# controller_02.net
KiCad netlist of a schematic drawn in EAGLE
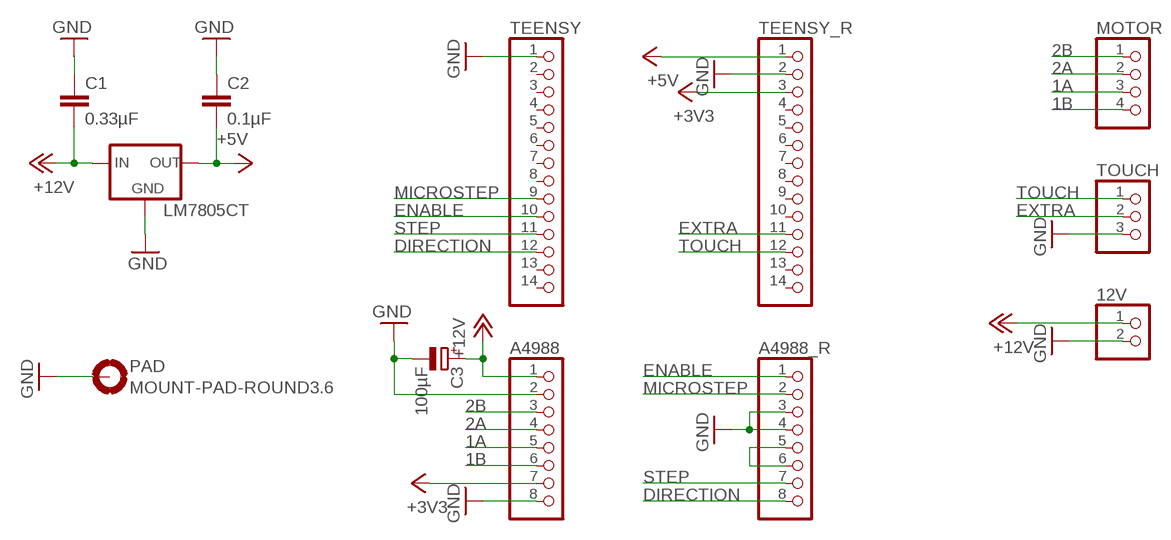
[diagram p0: schematic, sheet 1]

(export (version "E")
  (design (tool "Eeschema 10.0.6"))
  (components
    (comp (ref "12V")
      (value "PINHD-1X2")
      (footprint "eagle-import:1X02")
      (libsource (lib "eagle-import") (part "PINHD-1X2"))
    )
    (comp (ref "A4988")
      (value "PINHD-1X8")
      (footprint "eagle-import:1X08")
      (libsource (lib "eagle-import") (part "PINHD-1X8"))
    )
    (comp (ref "A4988_R")
      (value "PINHD-1X8")
      (footprint "eagle-import:1X08")
      (libsource (lib "eagle-import") (part "PINHD-1X8"))
    )
    (comp (ref "C1")
      (value "0.33µF")
      (footprint "eagle-import:C025-025X050")
      (libsource (lib "eagle-import") (part "C-EU025-025X050"))
    )
    (comp (ref "C2")
      (value "0.1µF")
      (footprint "eagle-import:C025-025X050")
      (libsource (lib "eagle-import") (part "C-EU025-025X050"))
    )
    (comp (ref "C3")
      (value "100µF")
      (footprint "eagle-import:E3,5-8")
      (libsource (lib "eagle-import") (part "CPOL-EUE3.5-8"))
    )
    (comp (ref "LM7805CT")
      (value "78XXL")
      (footprint "eagle-import:78XXL")
      (libsource (lib "eagle-import") (part "78XXL"))
    )
    (comp (ref "MOTOR")
      (value "PINHD-1X4")
      (footprint "eagle-import:1X04")
      (libsource (lib "eagle-import") (part "PINHD-1X4"))
    )
    (comp (ref "PAD")
      (value "MOUNT-PAD-ROUND3.6")
      (footprint "eagle-import:3,6-PAD")
      (libsource (lib "eagle-import") (part "MOUNT-PAD-ROUND3.6"))
    )
    (comp (ref "TEENSY")
      (value "PINHD-1X14")
      (footprint "eagle-import:1X14")
      (libsource (lib "eagle-import") (part "PINHD-1X14"))
    )
    (comp (ref "TEENSY_R")
      (value "PINHD-1X14")
      (footprint "eagle-import:1X14")
      (libsource (lib "eagle-import") (part "PINHD-1X14"))
    )
    (comp (ref "TOUCH")
      (value "PINHD-1X3")
      (footprint "eagle-import:1X03")
      (libsource (lib "eagle-import") (part "PINHD-1X3"))
    )
  )
  (nets
    (net (code "1") (name "+3V3") (class "Default")
      (node (ref "A4988") (pin "7") (pinfunction "7_7") (pintype "passive"))
      (node (ref "TEENSY_R") (pin "3") (pinfunction "3_3") (pintype "passive"))
    )
    (net (code "2") (name "+5V") (class "Default")
      (node (ref "C2") (pin "2") (pinfunction "2_2") (pintype "passive"))
      (node (ref "LM7805CT") (pin "OUT") (pinfunction "OUT_OUT") (pintype "passive"))
      (node (ref "TEENSY_R") (pin "1") (pinfunction "1_1") (pintype "passive"))
    )
    (net (code "3") (name "+12V") (class "Default")
      (node (ref "12V") (pin "1") (pinfunction "1_1") (pintype "passive"))
      (node (ref "A4988") (pin "1") (pinfunction "1_1") (pintype "passive"))
      (node (ref "C1") (pin "2") (pinfunction "2_2") (pintype "passive"))
      (node (ref "C3") (pin "+") (pinfunction "+_+") (pintype "passive"))
      (node (ref "LM7805CT") (pin "IN") (pinfunction "IN_IN") (pintype "input"))
    )
    (net (code "4") (name "/1A") (class "Default")
      (node (ref "A4988") (pin "5") (pinfunction "5_5") (pintype "passive"))
      (node (ref "MOTOR") (pin "3") (pinfunction "3_3") (pintype "passive"))
    )
    (net (code "5") (name "/1B") (class "Default")
      (node (ref "A4988") (pin "6") (pinfunction "6_6") (pintype "passive"))
      (node (ref "MOTOR") (pin "4") (pinfunction "4_4") (pintype "passive"))
    )
    (net (code "6") (name "/2A") (class "Default")
      (node (ref "A4988") (pin "4") (pinfunction "4_4") (pintype "passive"))
      (node (ref "MOTOR") (pin "2") (pinfunction "2_2") (pintype "passive"))
    )
    (net (code "7") (name "/2B") (class "Default")
      (node (ref "A4988") (pin "3") (pinfunction "3_3") (pintype "passive"))
      (node (ref "MOTOR") (pin "1") (pinfunction "1_1") (pintype "passive"))
    )
    (net (code "8") (name "/DIRECTION") (class "Default")
      (node (ref "A4988_R") (pin "8") (pinfunction "8_8") (pintype "passive"))
      (node (ref "TEENSY") (pin "12") (pinfunction "12_12") (pintype "passive"))
    )
    (net (code "9") (name "/ENABLE") (class "Default")
      (node (ref "A4988_R") (pin "1") (pinfunction "1_1") (pintype "passive"))
      (node (ref "TEENSY") (pin "10") (pinfunction "10_10") (pintype "passive"))
    )
    (net (code "10") (name "/EXTRA") (class "Default")
      (node (ref "TEENSY_R") (pin "11") (pinfunction "11_11") (pintype "passive"))
      (node (ref "TOUCH") (pin "2") (pinfunction "2_2") (pintype "passive"))
    )
    (net (code "11") (name "/MICROSTEP") (class "Default")
      (node (ref "A4988_R") (pin "2") (pinfunction "2_2") (pintype "passive"))
      (node (ref "TEENSY") (pin "9") (pinfunction "9_9") (pintype "passive"))
    )
    (net (code "12") (name "/STEP") (class "Default")
      (node (ref "A4988_R") (pin "7") (pinfunction "7_7") (pintype "passive"))
      (node (ref "TEENSY") (pin "11") (pinfunction "11_11") (pintype "passive"))
    )
    (net (code "13") (name "/TOUCH") (class "Default")
      (node (ref "TEENSY_R") (pin "12") (pinfunction "12_12") (pintype "passive"))
      (node (ref "TOUCH") (pin "1") (pinfunction "1_1") (pintype "passive"))
    )
    (net (code "14") (name "GND") (class "Default")
      (node (ref "12V") (pin "2") (pinfunction "2_2") (pintype "passive"))
      (node (ref "A4988") (pin "2") (pinfunction "2_2") (pintype "passive"))
      (node (ref "A4988") (pin "8") (pinfunction "8_8") (pintype "passive"))
      (node (ref "A4988_R") (pin "3") (pinfunction "3_3") (pintype "passive"))
      (node (ref "A4988_R") (pin "4") (pinfunction "4_4") (pintype "passive"))
      (node (ref "C1") (pin "1") (pinfunction "1_1") (pintype "passive"))
      (node (ref "C2") (pin "1") (pinfunction "1_1") (pintype "passive"))
      (node (ref "C3") (pin "-") (pinfunction "-_-") (pintype "passive"))
      (node (ref "LM7805CT") (pin "GND") (pinfunction "GND_GND") (pintype "input"))
      (node (ref "PAD") (pin "B3,6") (pinfunction "MOUNT_B3,6") (pintype "passive"))
      (node (ref "TEENSY") (pin "1") (pinfunction "1_1") (pintype "passive"))
      (node (ref "TEENSY_R") (pin "2") (pinfunction "2_2") (pintype "passive"))
      (node (ref "TOUCH") (pin "3") (pinfunction "3_3") (pintype "passive"))
    )
    (net (code "15") (name "Net-(A4988_R-Pad5)") (class "Default")
      (node (ref "A4988_R") (pin "5") (pinfunction "5_5") (pintype "passive"))
      (node (ref "A4988_R") (pin "6") (pinfunction "6_6") (pintype "passive"))
    )
    (net (code "16") (name "unconnected-(TEENSY-Pad2)") (class "Default")
      (node (ref "TEENSY") (pin "2") (pinfunction "2_2") (pintype "passive"))
    )
    (net (code "17") (name "unconnected-(TEENSY-Pad3)") (class "Default")
      (node (ref "TEENSY") (pin "3") (pinfunction "3_3") (pintype "passive"))
    )
    (net (code "18") (name "unconnected-(TEENSY-Pad4)") (class "Default")
      (node (ref "TEENSY") (pin "4") (pinfunction "4_4") (pintype "passive"))
    )
    (net (code "19") (name "unconnected-(TEENSY-Pad5)") (class "Default")
      (node (ref "TEENSY") (pin "5") (pinfunction "5_5") (pintype "passive"))
    )
    (net (code "20") (name "unconnected-(TEENSY-Pad6)") (class "Default")
      (node (ref "TEENSY") (pin "6") (pinfunction "6_6") (pintype "passive"))
    )
    (net (code "21") (name "unconnected-(TEENSY-Pad7)") (class "Default")
      (node (ref "TEENSY") (pin "7") (pinfunction "7_7") (pintype "passive"))
    )
    (net (code "22") (name "unconnected-(TEENSY-Pad8)") (class "Default")
      (node (ref "TEENSY") (pin "8") (pinfunction "8_8") (pintype "passive"))
    )
    (net (code "23") (name "unconnected-(TEENSY-Pad13)") (class "Default")
      (node (ref "TEENSY") (pin "13") (pinfunction "13_13") (pintype "passive"))
    )
    (net (code "24") (name "unconnected-(TEENSY-Pad14)") (class "Default")
      (node (ref "TEENSY") (pin "14") (pinfunction "14_14") (pintype "passive"))
    )
    (net (code "25") (name "unconnected-(TEENSY_R-Pad4)") (class "Default")
      (node (ref "TEENSY_R") (pin "4") (pinfunction "4_4") (pintype "passive"))
    )
    (net (code "26") (name "unconnected-(TEENSY_R-Pad5)") (class "Default")
      (node (ref "TEENSY_R") (pin "5") (pinfunction "5_5") (pintype "passive"))
    )
    (net (code "27") (name "unconnected-(TEENSY_R-Pad6)") (class "Default")
      (node (ref "TEENSY_R") (pin "6") (pinfunction "6_6") (pintype "passive"))
    )
    (net (code "28") (name "unconnected-(TEENSY_R-Pad7)") (class "Default")
      (node (ref "TEENSY_R") (pin "7") (pinfunction "7_7") (pintype "passive"))
    )
    (net (code "29") (name "unconnected-(TEENSY_R-Pad8)") (class "Default")
      (node (ref "TEENSY_R") (pin "8") (pinfunction "8_8") (pintype "passive"))
    )
    (net (code "30") (name "unconnected-(TEENSY_R-Pad9)") (class "Default")
      (node (ref "TEENSY_R") (pin "9") (pinfunction "9_9") (pintype "passive"))
    )
    (net (code "31") (name "unconnected-(TEENSY_R-Pad10)") (class "Default")
      (node (ref "TEENSY_R") (pin "10") (pinfunction "10_10") (pintype "passive"))
    )
    (net (code "32") (name "unconnected-(TEENSY_R-Pad13)") (class "Default")
      (node (ref "TEENSY_R") (pin "13") (pinfunction "13_13") (pintype "passive"))
    )
    (net (code "33") (name "unconnected-(TEENSY_R-Pad14)") (class "Default")
      (node (ref "TEENSY_R") (pin "14") (pinfunction "14_14") (pintype "passive"))
    )
  )
)
